# Sheet1.net
KiCad netlist of a schematic drawn in Altium Designer
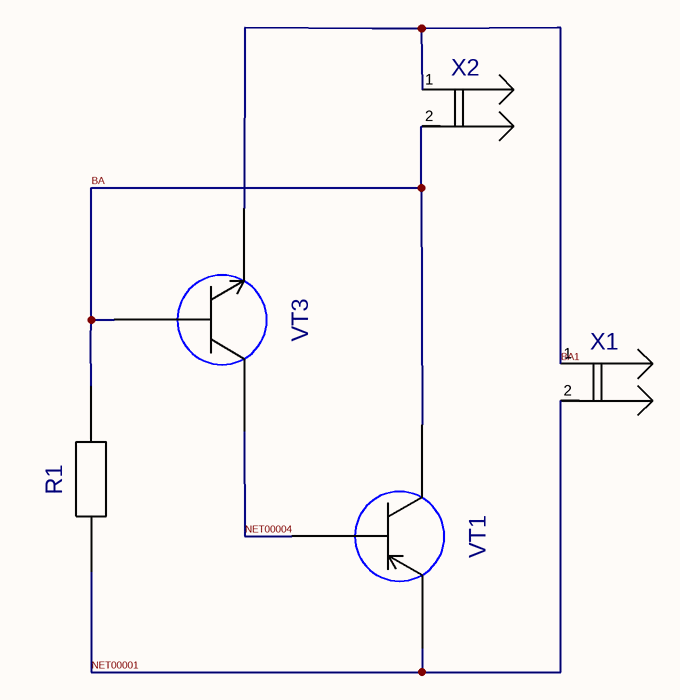
[diagram p0: Sheet1.SCHDOC]

(export (version "E")
  (design (tool "Eeschema 10.0.6"))
  (components
    (comp (ref "R1") (value "MURATA MF12") (footprint "RES400") (libsource (lib "*") (part "MURATA MF12")))
    (comp (ref "VT1") (value "КТ361") (footprint "КТ315") (libsource (lib "*") (part "КТ361")))
    (comp (ref "VT3") (value "КТ815") (footprint "КТ815") (libsource (lib "*") (part "КТ815")))
    (comp (ref "X1") (value "2XR") (footprint "2XR") (libsource (lib "*") (part "2XR")))
    (comp (ref "X2") (value "2XR") (footprint "2XR") (libsource (lib "*") (part "2XR")))
  )
  (nets
    (net (code "1") (name "/BA") (class "Default")
      (node (ref "R1") (pin "2") (pinfunction "A2_2") (pintype "passive"))
      (node (ref "VT1") (pin "2") (pinfunction "A2_2") (pintype "passive"))
      (node (ref "VT3") (pin "1") (pinfunction "A1_1") (pintype "passive"))
      (node (ref "X2") (pin "2") (pinfunction "I/O2_2") (pintype "passive"))
    )
    (net (code "2") (name "/BA1") (class "Default")
      (node (ref "VT3") (pin "3") (pinfunction "A3_3") (pintype "passive"))
      (node (ref "X1") (pin "1") (pinfunction "I/O1_1") (pintype "passive"))
      (node (ref "X2") (pin "1") (pinfunction "I/O1_1") (pintype "passive"))
    )
    (net (code "3") (name "/NET00001") (class "Default")
      (node (ref "R1") (pin "1") (pinfunction "A1_1") (pintype "passive"))
      (node (ref "VT1") (pin "3") (pinfunction "A3_3") (pintype "passive"))
      (node (ref "X1") (pin "2") (pinfunction "I/O2_2") (pintype "passive"))
    )
    (net (code "4") (name "/NET00004") (class "Default")
      (node (ref "VT1") (pin "1") (pinfunction "A1_1") (pintype "passive"))
      (node (ref "VT3") (pin "2") (pinfunction "A2_2") (pintype "passive"))
    )
  )
)
